# Extra_Parts.net
KiCad netlist of a schematic drawn in Altium Designer
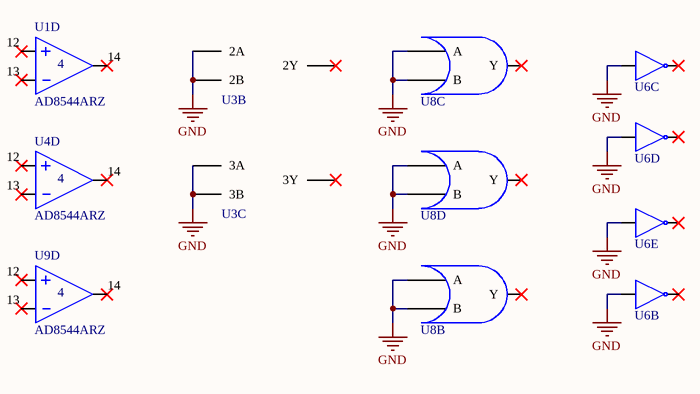
[diagram p0: Extra Parts.SchDoc]

(export (version "E")
  (design (tool "Eeschema 10.0.6"))
  (components
    (comp (ref "U1")
      (value "AD8544ARZ")
      (footprint "SOIC14P127_865X600X175L83X41N")
      (fields
        (field (name "PART NUMBER") "AD8544")
        (field (name "MANUFACTURER PART NUMBER") "AD8544ARZ-REEL")
      )
      (libsource (lib "FR") (part "AD8544"))
    )
    (comp (ref "U3")
      (value "HEF4081BT")
      (footprint "SOIC14P127_865X600X175L70X42N")
      (fields (field (name "MANUFACTURER PART NUMBER") "HEF4081BT,653"))
      (libsource (lib "FR") (part "HEF4081BT"))
    )
    (comp (ref "U4")
      (value "AD8544ARZ")
      (footprint "SOIC14P127_865X600X175L83X41N")
      (fields
        (field (name "PART NUMBER") "AD8544")
        (field (name "MANUFACTURER PART NUMBER") "AD8544ARZ-REEL")
      )
      (libsource (lib "FR") (part "AD8544"))
    )
    (comp (ref "U6")
      (value "HCF40106YM013TR")
      (footprint "SOIC14P127_865X600X175L88X40N")
      (fields (field (name "PART NUMBER") "HCF40106"))
      (libsource (lib "FR") (part "HCF40106"))
    )
    (comp (ref "U8")
      (value "CD4071BM")
      (footprint "SOIC14P127_865X600X175L70X42N")
      (libsource (lib "FR") (part "HEF4071B"))
    )
    (comp (ref "U9")
      (value "AD8544ARZ")
      (footprint "SOIC14P127_865X600X175L83X41N")
      (fields
        (field (name "PART NUMBER") "AD8544")
        (field (name "MANUFACTURER PART NUMBER") "AD8544ARZ-REEL")
      )
      (libsource (lib "FR") (part "AD8544"))
    )
  )
  (nets
    (net (code "1") (name "GND") (class "Default")
      (node (ref "U3") (pin "5") (pinfunction "2A_5") (pintype "passive"))
      (node (ref "U3") (pin "6") (pinfunction "2B_6") (pintype "passive"))
      (node (ref "U3") (pin "8") (pinfunction "3A_8") (pintype "passive"))
      (node (ref "U3") (pin "9") (pinfunction "3B_9") (pintype "passive"))
      (node (ref "U6") (pin "11") (pinfunction "E_11") (pintype "passive"))
      (node (ref "U6") (pin "3") (pinfunction "B_3") (pintype "passive"))
      (node (ref "U6") (pin "5") (pinfunction "C_5") (pintype "passive"))
      (node (ref "U6") (pin "9") (pinfunction "D_9") (pintype "passive"))
      (node (ref "U8") (pin "12") (pinfunction "A_12") (pintype "passive"))
      (node (ref "U8") (pin "13") (pinfunction "B_13") (pintype "passive"))
      (node (ref "U8") (pin "5") (pinfunction "A_5") (pintype "passive"))
      (node (ref "U8") (pin "6") (pinfunction "B_6") (pintype "passive"))
      (node (ref "U8") (pin "8") (pinfunction "A_8") (pintype "passive"))
      (node (ref "U8") (pin "9") (pinfunction "B_9") (pintype "passive"))
    )
    (net (code "2") (name "unconnected-(U1-Pad12)") (class "Default")
      (node (ref "U1") (pin "12") (pintype "passive+no_connect"))
    )
    (net (code "3") (name "unconnected-(U1-Pad13)") (class "Default")
      (node (ref "U1") (pin "13") (pintype "passive+no_connect"))
    )
    (net (code "4") (name "unconnected-(U1-Pad14)") (class "Default")
      (node (ref "U1") (pin "14") (pintype "passive+no_connect"))
    )
    (net (code "5") (name "unconnected-(U3B-2Y-Pad4)") (class "Default")
      (node (ref "U3") (pin "4") (pinfunction "2Y_4") (pintype "passive+no_connect"))
    )
    (net (code "6") (name "unconnected-(U3C-3Y-Pad10)") (class "Default")
      (node (ref "U3") (pin "10") (pinfunction "3Y_10") (pintype "passive+no_connect"))
    )
    (net (code "7") (name "unconnected-(U4-Pad12)") (class "Default")
      (node (ref "U4") (pin "12") (pintype "passive+no_connect"))
    )
    (net (code "8") (name "unconnected-(U4-Pad13)") (class "Default")
      (node (ref "U4") (pin "13") (pintype "passive+no_connect"))
    )
    (net (code "9") (name "unconnected-(U4-Pad14)") (class "Default")
      (node (ref "U4") (pin "14") (pintype "passive+no_connect"))
    )
    (net (code "10") (name "unconnected-(U6B-H-Pad4)") (class "Default")
      (node (ref "U6") (pin "4") (pinfunction "H_4") (pintype "passive+no_connect"))
    )
    (net (code "11") (name "unconnected-(U6C-I-Pad6)") (class "Default")
      (node (ref "U6") (pin "6") (pinfunction "I_6") (pintype "passive+no_connect"))
    )
    (net (code "12") (name "unconnected-(U6D-J-Pad8)") (class "Default")
      (node (ref "U6") (pin "8") (pinfunction "J_8") (pintype "passive+no_connect"))
    )
    (net (code "13") (name "unconnected-(U6E-K-Pad10)") (class "Default")
      (node (ref "U6") (pin "10") (pinfunction "K_10") (pintype "passive+no_connect"))
    )
    (net (code "14") (name "unconnected-(U8B-Y-Pad4)") (class "Default")
      (node (ref "U8") (pin "4") (pinfunction "Y_4") (pintype "passive+no_connect"))
    )
    (net (code "15") (name "unconnected-(U8C-Y-Pad10)") (class "Default")
      (node (ref "U8") (pin "10") (pinfunction "Y_10") (pintype "passive+no_connect"))
    )
    (net (code "16") (name "unconnected-(U8D-Y-Pad11)") (class "Default")
      (node (ref "U8") (pin "11") (pinfunction "Y_11") (pintype "passive+no_connect"))
    )
    (net (code "17") (name "unconnected-(U9-Pad12)") (class "Default")
      (node (ref "U9") (pin "12") (pintype "passive+no_connect"))
    )
    (net (code "18") (name "unconnected-(U9-Pad13)") (class "Default")
      (node (ref "U9") (pin "13") (pintype "passive+no_connect"))
    )
    (net (code "19") (name "unconnected-(U9-Pad14)") (class "Default")
      (node (ref "U9") (pin "14") (pintype "passive+no_connect"))
    )
  )
)
